# Tracker.net
KiCad netlist of a schematic drawn in EAGLE
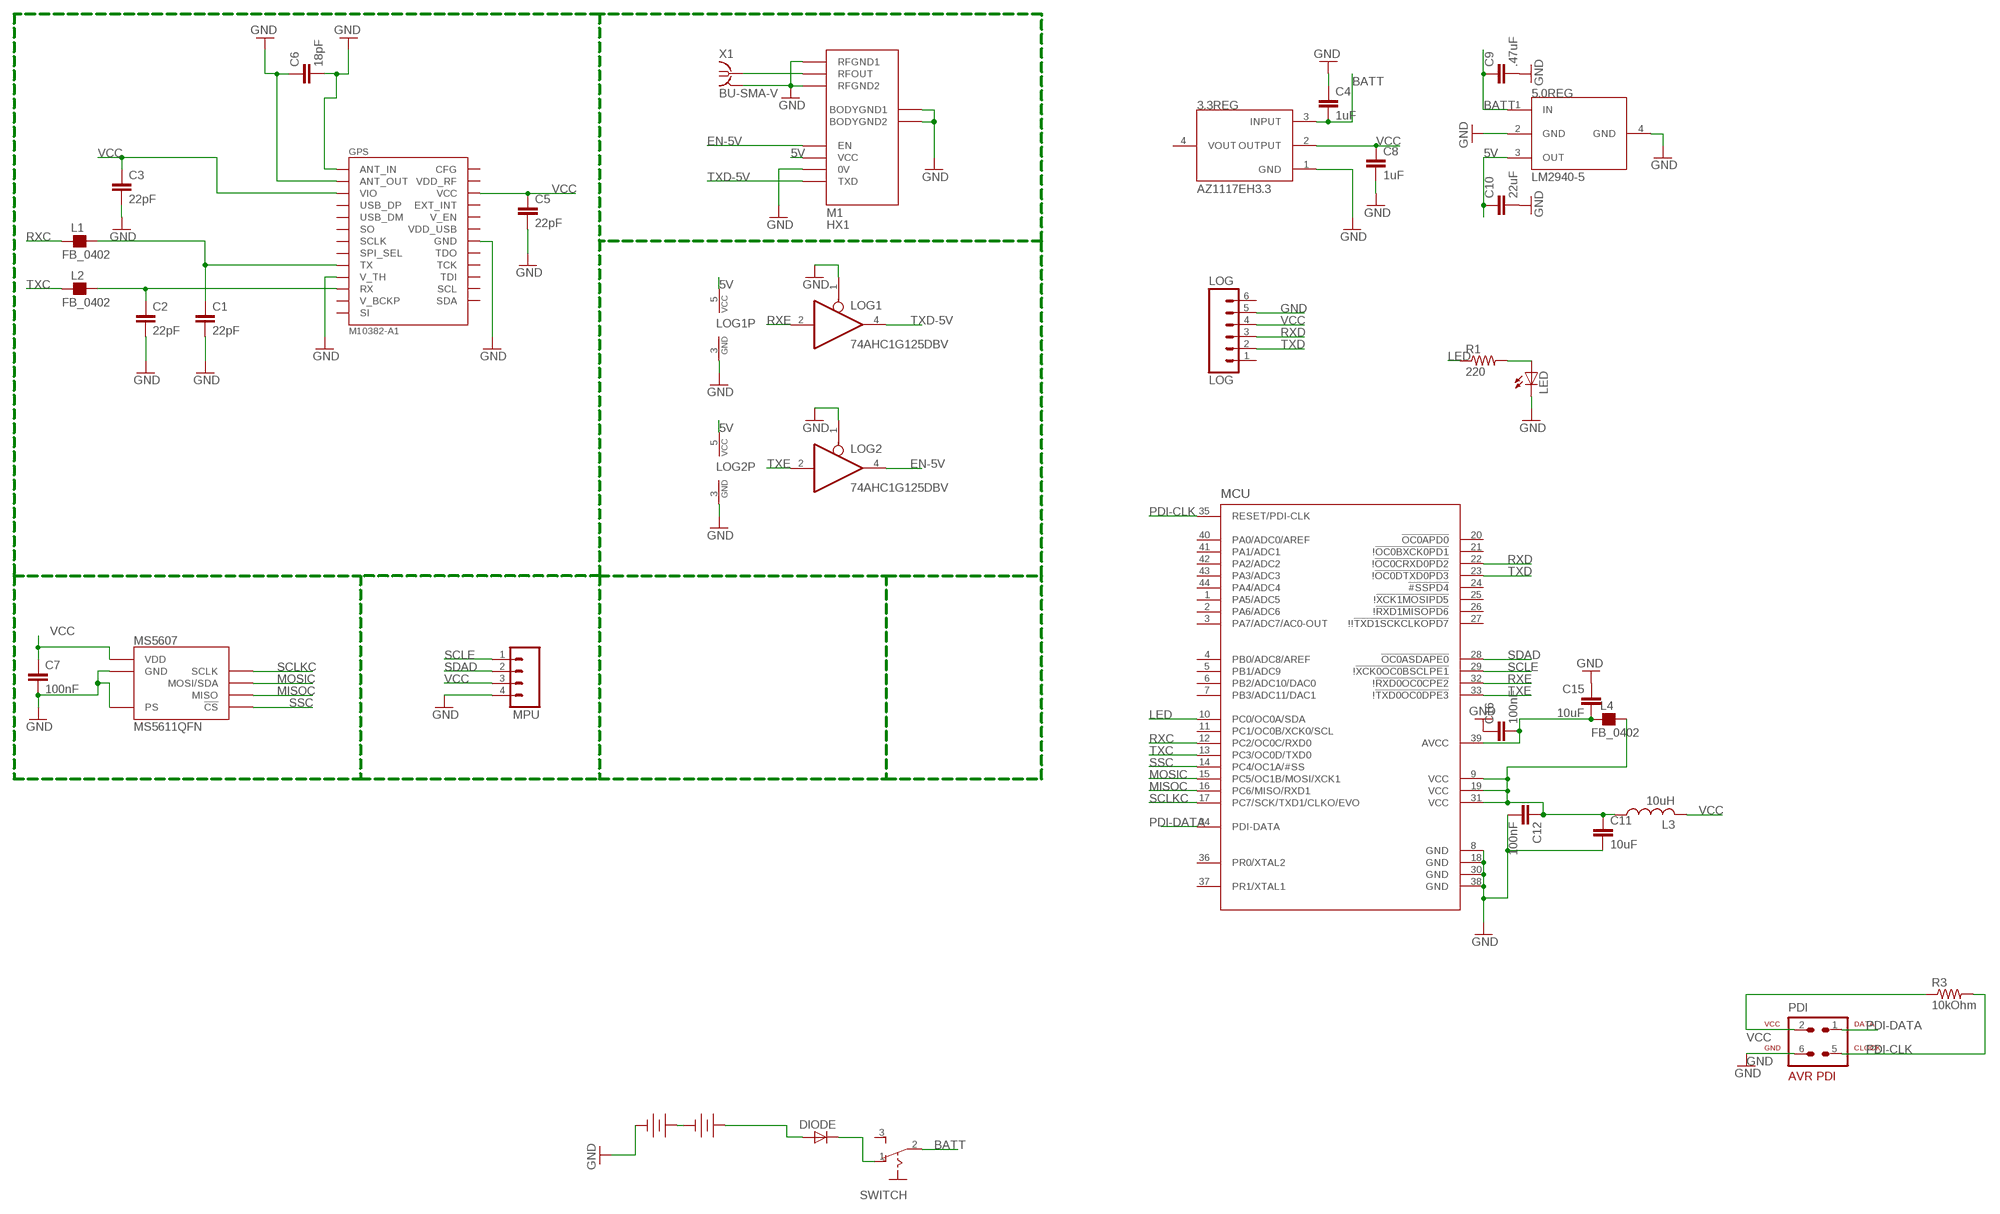
[diagram p0: schematic, sheet 1]

(export (version "E")
  (design (tool "Eeschema 10.0.6"))
  (components
    (comp (ref "3.3REG")
      (value "AZ1117EH3.3")
      (footprint "eagle-import:SOT-223")
      (libsource (lib "eagle-import") (part "AZ1117EH3.3"))
    )
    (comp (ref "5.0REG")
      (value "LM2940-5")
      (footprint "eagle-import:SOT-223")
      (libsource (lib "eagle-import") (part "LM2940-5"))
    )
    (comp (ref "BATT1")
      (value "123_BATTERY_HOLDERCR-123-A")
      (footprint "eagle-import:CR-123-A_HOLDER")
      (libsource (lib "eagle-import") (part "123_BATTERY_HOLDERCR-123-A"))
    )
    (comp (ref "BATT2")
      (value "123_BATTERY_HOLDERCR-123-A")
      (footprint "eagle-import:CR-123-A_HOLDER")
      (libsource (lib "eagle-import") (part "123_BATTERY_HOLDERCR-123-A"))
    )
    (comp (ref "C1")
      (value "22pF")
      (footprint "eagle-import:0805")
      (libsource (lib "eagle-import") (part "CAP0805"))
    )
    (comp (ref "C2")
      (value "22pF")
      (footprint "eagle-import:0805")
      (libsource (lib "eagle-import") (part "CAP0805"))
    )
    (comp (ref "C3")
      (value "22pF")
      (footprint "eagle-import:0805")
      (libsource (lib "eagle-import") (part "CAP0805"))
    )
    (comp (ref "C4")
      (value "1uF")
      (footprint "eagle-import:0603-CAP")
      (libsource (lib "eagle-import") (part "CAP0603-CAP"))
    )
    (comp (ref "C5")
      (value "22pF")
      (footprint "eagle-import:0805")
      (libsource (lib "eagle-import") (part "CAP0805"))
    )
    (comp (ref "C6")
      (value "18pF")
      (footprint "eagle-import:0805")
      (libsource (lib "eagle-import") (part "CAP0805"))
    )
    (comp (ref "C7")
      (value "100nF")
      (footprint "eagle-import:0805")
      (libsource (lib "eagle-import") (part "CAP0805"))
    )
    (comp (ref "C8")
      (value "1uF")
      (footprint "eagle-import:0603-CAP")
      (libsource (lib "eagle-import") (part "CAP0603-CAP"))
    )
    (comp (ref "C9")
      (value ".47uF")
      (footprint "eagle-import:0603-CAP")
      (libsource (lib "eagle-import") (part "CAP0603-CAP"))
    )
    (comp (ref "C10")
      (value "22uF")
      (footprint "eagle-import:0603-CAP")
      (libsource (lib "eagle-import") (part "CAP0603-CAP"))
    )
    (comp (ref "C11")
      (value "10uF")
      (footprint "eagle-import:0805")
      (libsource (lib "eagle-import") (part "CAP0805"))
    )
    (comp (ref "C12")
      (value "100nF")
      (footprint "eagle-import:0805")
      (libsource (lib "eagle-import") (part "CAP0805"))
    )
    (comp (ref "C15")
      (value "10uF")
      (footprint "eagle-import:0805")
      (libsource (lib "eagle-import") (part "CAP0805"))
    )
    (comp (ref "C16")
      (value "100nF")
      (footprint "eagle-import:0805")
      (libsource (lib "eagle-import") (part "CAP0805"))
    )
    (comp (ref "DIODE")
      (value "LILYPAD-WEARABLES_LED1206")
      (footprint "eagle-import:LILYPAD-WEARABLES_LED-1206")
      (libsource (lib "eagle-import") (part "LILYPAD-WEARABLES_LED1206"))
    )
    (comp (ref "GPS")
      (value "M10382-A1")
      (footprint "eagle-import:M10382-A1")
      (libsource (lib "eagle-import") (part "M10382-A1"))
    )
    (comp (ref "L1")
      (value "FB_0402")
      (footprint "eagle-import:L0402")
      (libsource (lib "eagle-import") (part "FB_0402"))
    )
    (comp (ref "L2")
      (value "FB_0402")
      (footprint "eagle-import:L0402")
      (libsource (lib "eagle-import") (part "FB_0402"))
    )
    (comp (ref "L3")
      (value "10uH")
      (footprint "eagle-import:L2012C")
      (libsource (lib "eagle-import") (part "L-USL2012C"))
    )
    (comp (ref "L4")
      (value "FB_0402")
      (footprint "eagle-import:L0402")
      (libsource (lib "eagle-import") (part "FB_0402"))
    )
    (comp (ref "LED")
      (value "LEDCHIP-LED0603")
      (footprint "eagle-import:CHIP-LED0603")
      (libsource (lib "eagle-import") (part "LEDCHIP-LED0603"))
    )
    (comp (ref "LOG")
      (value "LOG")
      (footprint "eagle-import:SPARKFUN_1X06")
      (libsource (lib "eagle-import") (part "SPARKFUN_M06SIP"))
    )
    (comp (ref "LOG1")
      (value "74AHC1G125DBV")
      (footprint "eagle-import:SOT23-5")
      (libsource (lib "eagle-import") (part "741G125DBVAHC"))
    )
    (comp (ref "LOG2")
      (value "74AHC1G125DBV")
      (footprint "eagle-import:SOT23-5")
      (libsource (lib "eagle-import") (part "741G125DBVAHC"))
    )
    (comp (ref "M1")
      (value "HX1")
      (footprint "eagle-import:HX1")
      (libsource (lib "eagle-import") (part "HX1"))
    )
    (comp (ref "MCU")
      (value "AT-XMEGA-XXA4-AU")
      (footprint "eagle-import:QFP80P1200X1200X120-44N")
      (libsource (lib "eagle-import") (part "AT-XMEGA-XXA4-AU"))
    )
    (comp (ref "MPU")
      (value "M04")
      (footprint "eagle-import:04P")
      (libsource (lib "eagle-import") (part "M04"))
    )
    (comp (ref "MS5607")
      (value "MS5611QFN")
      (footprint "eagle-import:MS5611-01BA01")
      (libsource (lib "eagle-import") (part "MS5611QFN"))
    )
    (comp (ref "PDI")
      (value "AVR-7_AVR-PDIVERT")
      (footprint "eagle-import:AVR-7_AVR-ISP-6")
      (libsource (lib "eagle-import") (part "AVR-7_AVR-PDIVERT"))
    )
    (comp (ref "R1")
      (value "220")
      (footprint "eagle-import:R0603")
      (libsource (lib "eagle-import") (part "R-US_R0603"))
    )
    (comp (ref "R3")
      (value "10kOhm")
      (footprint "eagle-import:0805")
      (libsource (lib "eagle-import") (part "RESISTOR0805-RES"))
    )
    (comp (ref "SWITCH")
      (value "M251")
      (footprint "eagle-import:M251")
      (libsource (lib "eagle-import") (part "M251"))
    )
    (comp (ref "X1")
      (value "BU-SMA-V")
      (footprint "eagle-import:BU-SMA-V")
      (libsource (lib "eagle-import") (part "BU-SMA-V"))
    )
  )
  (nets
    (net (code "1") (name "/5V") (class "Default")
      (node (ref "5.0REG") (pin "3") (pinfunction "OUT_3") (pintype "bidirectional"))
      (node (ref "C10") (pin "1") (pinfunction "1_1") (pintype "passive"))
      (node (ref "LOG1") (pin "5") (pinfunction "VCC_5") (pintype "power_in"))
      (node (ref "LOG2") (pin "5") (pinfunction "VCC_5") (pintype "power_in"))
      (node (ref "M1") (pin "VCC") (pinfunction "VCC_VCC") (pintype "bidirectional"))
    )
    (net (code "2") (name "/BATT") (class "Default")
      (node (ref "3.3REG") (pin "3") (pinfunction "INPUT_3") (pintype "bidirectional"))
      (node (ref "5.0REG") (pin "1") (pinfunction "IN_1") (pintype "bidirectional"))
      (node (ref "C4") (pin "2") (pinfunction "2_2") (pintype "passive"))
      (node (ref "C9") (pin "1") (pinfunction "1_1") (pintype "passive"))
      (node (ref "SWITCH") (pin "2") (pinfunction "P_2") (pintype "passive"))
    )
    (net (code "3") (name "/EN-5V") (class "Default")
      (node (ref "LOG2") (pin "4") (pinfunction "O_4") (pintype "tri_state"))
      (node (ref "M1") (pin "EN") (pinfunction "EN_EN") (pintype "bidirectional"))
    )
    (net (code "4") (name "/LED") (class "Default")
      (node (ref "MCU") (pin "10") (pinfunction "PC0/OC0A/SDA_10") (pintype "bidirectional"))
      (node (ref "R1") (pin "1") (pinfunction "1_1") (pintype "passive"))
    )
    (net (code "5") (name "/MISOC") (class "Default")
      (node (ref "MCU") (pin "16") (pinfunction "PC6/MISO/RXD1_16") (pintype "bidirectional"))
      (node (ref "MS5607") (pin "6") (pinfunction "MISO_6") (pintype "bidirectional"))
    )
    (net (code "6") (name "/MOSIC") (class "Default")
      (node (ref "MCU") (pin "15") (pinfunction "PC5/OC1B/MOSI/XCK1_15") (pintype "bidirectional"))
      (node (ref "MS5607") (pin "7") (pinfunction "MOSI/SDA_7") (pintype "bidirectional"))
    )
    (net (code "7") (name "/PDI-CLK") (class "Default")
      (node (ref "MCU") (pin "35") (pinfunction "RESET/PDI-CLK_35") (pintype "input"))
      (node (ref "PDI") (pin "5") (pinfunction "5_5") (pintype "passive"))
      (node (ref "R3") (pin "2") (pinfunction "2_2") (pintype "passive"))
    )
    (net (code "8") (name "/PDI-DATA") (class "Default")
      (node (ref "MCU") (pin "34") (pinfunction "PDI-DATA_34") (pintype "bidirectional"))
      (node (ref "PDI") (pin "1") (pinfunction "1_1") (pintype "passive"))
    )
    (net (code "9") (name "/RXC") (class "Default")
      (node (ref "L1") (pin "1") (pinfunction "1_1") (pintype "passive"))
      (node (ref "MCU") (pin "12") (pinfunction "PC2/OC0C/RXD0_12") (pintype "bidirectional"))
    )
    (net (code "10") (name "/RXD") (class "Default")
      (node (ref "LOG") (pin "3") (pinfunction "3_3") (pintype "passive"))
      (node (ref "MCU") (pin "22") (pinfunction "~OC0CRXD0PD2_22") (pintype "bidirectional"))
    )
    (net (code "11") (name "/RXE") (class "Default")
      (node (ref "LOG1") (pin "2") (pinfunction "I_2") (pintype "input"))
      (node (ref "MCU") (pin "32") (pinfunction "~RXD0OC0CPE2_32") (pintype "bidirectional"))
    )
    (net (code "12") (name "/SCLE") (class "Default")
      (node (ref "MCU") (pin "29") (pinfunction "~XCK0OC0BSCLPE1_29") (pintype "bidirectional"))
      (node (ref "MPU") (pin "1") (pinfunction "1_1") (pintype "passive"))
    )
    (net (code "13") (name "/SCLKC") (class "Default")
      (node (ref "MCU") (pin "17") (pinfunction "PC7/SCK/TXD1/CLKO/EVO_17") (pintype "bidirectional"))
      (node (ref "MS5607") (pin "8") (pinfunction "SCLK_8") (pintype "bidirectional"))
    )
    (net (code "14") (name "/SDAD") (class "Default")
      (node (ref "MCU") (pin "28") (pinfunction "~{OC0ASDAPE0}_28") (pintype "bidirectional"))
      (node (ref "MPU") (pin "2") (pinfunction "2_2") (pintype "passive"))
    )
    (net (code "15") (name "/SSC") (class "Default")
      (node (ref "MCU") (pin "14") (pinfunction "PC4/OC1A/#SS_14") (pintype "bidirectional"))
      (node (ref "MS5607") (pin "4") (pinfunction "~{CS}_4") (pintype "bidirectional"))
      (node (ref "MS5607") (pin "5") (pinfunction "~{CS}_5") (pintype "bidirectional"))
    )
    (net (code "16") (name "/TXC") (class "Default")
      (node (ref "L2") (pin "1") (pinfunction "1_1") (pintype "passive"))
      (node (ref "MCU") (pin "13") (pinfunction "PC3/OC0D/TXD0_13") (pintype "bidirectional"))
    )
    (net (code "17") (name "/TXD") (class "Default")
      (node (ref "LOG") (pin "2") (pinfunction "2_2") (pintype "passive"))
      (node (ref "MCU") (pin "23") (pinfunction "~OC0DTXD0PD3_23") (pintype "bidirectional"))
    )
    (net (code "18") (name "/TXD-5V") (class "Default")
      (node (ref "LOG1") (pin "4") (pinfunction "O_4") (pintype "tri_state"))
      (node (ref "M1") (pin "TXD") (pinfunction "TXD_TXD") (pintype "bidirectional"))
    )
    (net (code "19") (name "/TXE") (class "Default")
      (node (ref "LOG2") (pin "2") (pinfunction "I_2") (pintype "input"))
      (node (ref "MCU") (pin "33") (pinfunction "~TXD0OC0DPE3_33") (pintype "bidirectional"))
    )
    (net (code "20") (name "/VCC") (class "Default")
      (node (ref "3.3REG") (pin "2") (pinfunction "OUTPUT_2") (pintype "bidirectional"))
      (node (ref "C3") (pin "1") (pinfunction "1_1") (pintype "passive"))
      (node (ref "C5") (pin "1") (pinfunction "1_1") (pintype "passive"))
      (node (ref "C7") (pin "1") (pinfunction "1_1") (pintype "passive"))
      (node (ref "C8") (pin "1") (pinfunction "1_1") (pintype "passive"))
      (node (ref "GPS") (pin "27") (pinfunction "VCC_27") (pintype "bidirectional"))
      (node (ref "GPS") (pin "5") (pinfunction "VIO_5") (pintype "bidirectional"))
      (node (ref "L3") (pin "2") (pinfunction "2_2") (pintype "passive"))
      (node (ref "LOG") (pin "4") (pinfunction "4_4") (pintype "passive"))
      (node (ref "MPU") (pin "3") (pinfunction "3_3") (pintype "passive"))
      (node (ref "MS5607") (pin "1") (pinfunction "VDD_1") (pintype "bidirectional"))
      (node (ref "PDI") (pin "2") (pinfunction "2_2") (pintype "passive"))
      (node (ref "R3") (pin "1") (pinfunction "1_1") (pintype "passive"))
    )
    (net (code "21") (name "GND") (class "Default")
      (node (ref "3.3REG") (pin "1") (pinfunction "GND_1") (pintype "bidirectional"))
      (node (ref "5.0REG") (pin "2") (pinfunction "GND_2") (pintype "bidirectional"))
      (node (ref "5.0REG") (pin "4") (pinfunction "GND_4") (pintype "bidirectional"))
      (node (ref "BATT2") (pin "-") (pinfunction "-_-") (pintype "bidirectional"))
      (node (ref "C1") (pin "2") (pinfunction "2_2") (pintype "passive"))
      (node (ref "C10") (pin "2") (pinfunction "2_2") (pintype "passive"))
      (node (ref "C11") (pin "2") (pinfunction "2_2") (pintype "passive"))
      (node (ref "C12") (pin "2") (pinfunction "2_2") (pintype "passive"))
      (node (ref "C15") (pin "1") (pinfunction "1_1") (pintype "passive"))
      (node (ref "C16") (pin "1") (pinfunction "1_1") (pintype "passive"))
      (node (ref "C2") (pin "2") (pinfunction "2_2") (pintype "passive"))
      (node (ref "C3") (pin "2") (pinfunction "2_2") (pintype "passive"))
      (node (ref "C4") (pin "1") (pinfunction "1_1") (pintype "passive"))
      (node (ref "C5") (pin "2") (pinfunction "2_2") (pintype "passive"))
      (node (ref "C6") (pin "1") (pinfunction "1_1") (pintype "passive"))
      (node (ref "C6") (pin "2") (pinfunction "2_2") (pintype "passive"))
      (node (ref "C7") (pin "2") (pinfunction "2_2") (pintype "passive"))
      (node (ref "C8") (pin "2") (pinfunction "2_2") (pintype "passive"))
      (node (ref "C9") (pin "2") (pinfunction "2_2") (pintype "passive"))
      (node (ref "GPS") (pin "1") (pinfunction "ANT_IN_1") (pintype "bidirectional"))
      (node (ref "GPS") (pin "12") (pinfunction "V_TH_12") (pintype "bidirectional"))
      (node (ref "GPS") (pin "14") (pinfunction "GND_14") (pintype "bidirectional"))
      (node (ref "GPS") (pin "17") (pinfunction "GND_17") (pintype "bidirectional"))
      (node (ref "GPS") (pin "2") (pinfunction "GND_2") (pintype "bidirectional"))
      (node (ref "GPS") (pin "21") (pinfunction "GND_21") (pintype "bidirectional"))
      (node (ref "GPS") (pin "24") (pinfunction "GND_24") (pintype "bidirectional"))
      (node (ref "GPS") (pin "26") (pinfunction "GND_26") (pintype "bidirectional"))
      (node (ref "GPS") (pin "28") (pinfunction "GND_28") (pintype "bidirectional"))
      (node (ref "GPS") (pin "3") (pinfunction "ANT_OUT_3") (pintype "bidirectional"))
      (node (ref "GPS") (pin "33") (pinfunction "GND_33") (pintype "bidirectional"))
      (node (ref "GPS") (pin "34") (pinfunction "GND_34") (pintype "bidirectional"))
      (node (ref "GPS") (pin "35") (pinfunction "GND_35") (pintype "bidirectional"))
      (node (ref "GPS") (pin "36") (pinfunction "GND_36") (pintype "bidirectional"))
      (node (ref "GPS") (pin "4") (pinfunction "GND_4") (pintype "bidirectional"))
      (node (ref "LED") (pin "C") (pinfunction "C_C") (pintype "passive"))
      (node (ref "LOG") (pin "5") (pinfunction "5_5") (pintype "passive"))
      (node (ref "LOG1") (pin "1") (pinfunction "OE_1") (pintype "input"))
      (node (ref "LOG1") (pin "3") (pinfunction "GND_3") (pintype "power_in"))
      (node (ref "LOG2") (pin "1") (pinfunction "OE_1") (pintype "input"))
      (node (ref "LOG2") (pin "3") (pinfunction "GND_3") (pintype "power_in"))
      (node (ref "M1") (pin "0V") (pinfunction "0V_0V") (pintype "bidirectional"))
      (node (ref "M1") (pin "BODYGND1") (pinfunction "BODYGND1_BODYGND1") (pintype "bidirectional"))
      (node (ref "M1") (pin "BODYGND2") (pinfunction "BODYGND2_BODYGND2") (pintype "bidirectional"))
      (node (ref "M1") (pin "RFGND1") (pinfunction "RFGND1_RFGND1") (pintype "bidirectional"))
      (node (ref "M1") (pin "RFGND2") (pinfunction "RFGND2_RFGND2") (pintype "bidirectional"))
      (node (ref "MCU") (pin "18") (pinfunction "GND_18") (pintype "power_in"))
      (node (ref "MCU") (pin "30") (pinfunction "GND_30") (pintype "power_in"))
      (node (ref "MCU") (pin "38") (pinfunction "GND_38") (pintype "power_in"))
      (node (ref "MCU") (pin "8") (pinfunction "GND_8") (pintype "power_in"))
      (node (ref "MPU") (pin "4") (pinfunction "4_4") (pintype "passive"))
      (node (ref "MS5607") (pin "2") (pinfunction "PS_2") (pintype "bidirectional"))
      (node (ref "MS5607") (pin "3") (pinfunction "GND_3") (pintype "bidirectional"))
      (node (ref "PDI") (pin "6") (pinfunction "6_6") (pintype "passive"))
      (node (ref "X1") (pin "2") (pinfunction "GND_2") (pintype "power_in"))
    )
    (net (code "22") (name "Net-(BATT1-Pad+)") (class "Default")
      (node (ref "BATT1") (pin "+") (pinfunction "+_+") (pintype "bidirectional"))
      (node (ref "DIODE") (pin "A") (pinfunction "A_A") (pintype "passive"))
    )
    (net (code "23") (name "Net-(BATT1-Pad-)") (class "Default")
      (node (ref "BATT1") (pin "-") (pinfunction "-_-") (pintype "bidirectional"))
      (node (ref "BATT2") (pin "+") (pinfunction "+_+") (pintype "bidirectional"))
    )
    (net (code "24") (name "Net-(C11-Pad1)") (class "Default")
      (node (ref "C11") (pin "1") (pinfunction "1_1") (pintype "passive"))
      (node (ref "C12") (pin "1") (pinfunction "1_1") (pintype "passive"))
      (node (ref "L3") (pin "1") (pinfunction "1_1") (pintype "passive"))
      (node (ref "L4") (pin "2") (pinfunction "2_2") (pintype "passive"))
      (node (ref "MCU") (pin "19") (pinfunction "VCC_19") (pintype "power_in"))
      (node (ref "MCU") (pin "31") (pinfunction "VCC_31") (pintype "power_in"))
      (node (ref "MCU") (pin "9") (pinfunction "VCC_9") (pintype "power_in"))
    )
    (net (code "25") (name "Net-(GPS-RX)") (class "Default")
      (node (ref "C2") (pin "1") (pinfunction "1_1") (pintype "passive"))
      (node (ref "GPS") (pin "13") (pinfunction "RX_13") (pintype "bidirectional"))
      (node (ref "L2") (pin "2") (pinfunction "2_2") (pintype "passive"))
    )
    (net (code "26") (name "Net-(GPS-TX)") (class "Default")
      (node (ref "C1") (pin "1") (pinfunction "1_1") (pintype "passive"))
      (node (ref "GPS") (pin "11") (pinfunction "TX_11") (pintype "bidirectional"))
      (node (ref "L1") (pin "2") (pinfunction "2_2") (pintype "passive"))
    )
    (net (code "27") (name "Net-(LED-PadA)") (class "Default")
      (node (ref "LED") (pin "A") (pinfunction "A_A") (pintype "passive"))
      (node (ref "R1") (pin "2") (pinfunction "2_2") (pintype "passive"))
    )
    (net (code "28") (name "Net-(M1-PadRFOUT)") (class "Default")
      (node (ref "M1") (pin "RFOUT") (pinfunction "RFOUT_RFOUT") (pintype "bidirectional"))
      (node (ref "X1") (pin "1") (pinfunction "1_1") (pintype "passive"))
    )
    (net (code "29") (name "Net-(MCU-AVCC)") (class "Default")
      (node (ref "C15") (pin "2") (pinfunction "2_2") (pintype "passive"))
      (node (ref "C16") (pin "2") (pinfunction "2_2") (pintype "passive"))
      (node (ref "L4") (pin "1") (pinfunction "1_1") (pintype "passive"))
      (node (ref "MCU") (pin "39") (pinfunction "AVCC_39") (pintype "power_in"))
    )
    (net (code "30") (name "Net-(SWITCH-O)") (class "Default")
      (node (ref "DIODE") (pin "C") (pinfunction "C_C") (pintype "passive"))
      (node (ref "SWITCH") (pin "1") (pinfunction "O_1") (pintype "passive"))
    )
    (net (code "31") (name "unconnected-(3.3REG-VOUT-Pad4)") (class "Default")
      (node (ref "3.3REG") (pin "4") (pinfunction "VOUT_4") (pintype "bidirectional"))
    )
    (net (code "32") (name "unconnected-(GPS-CFG-Pad31)") (class "Default")
      (node (ref "GPS") (pin "31") (pinfunction "CFG_31") (pintype "bidirectional"))
    )
    (net (code "33") (name "unconnected-(GPS-EXT_INT-Pad29)") (class "Default")
      (node (ref "GPS") (pin "29") (pinfunction "EXT_INT_29") (pintype "bidirectional"))
    )
    (net (code "34") (name "unconnected-(GPS-SCL-Pad19)") (class "Default")
      (node (ref "GPS") (pin "19") (pinfunction "SCL_19") (pintype "bidirectional"))
    )
    (net (code "35") (name "unconnected-(GPS-SCLK-Pad9)") (class "Default")
      (node (ref "GPS") (pin "9") (pinfunction "SCLK_9") (pintype "bidirectional"))
    )
    (net (code "36") (name "unconnected-(GPS-SDA-Pad18)") (class "Default")
      (node (ref "GPS") (pin "18") (pinfunction "SDA_18") (pintype "bidirectional"))
    )
    (net (code "37") (name "unconnected-(GPS-SI-Pad16)") (class "Default")
      (node (ref "GPS") (pin "16") (pinfunction "SI_16") (pintype "bidirectional"))
    )
    (net (code "38") (name "unconnected-(GPS-SO-Pad8)") (class "Default")
      (node (ref "GPS") (pin "8") (pinfunction "SO_8") (pintype "bidirectional"))
    )
    (net (code "39") (name "unconnected-(GPS-SPI_SEL-Pad10)") (class "Default")
      (node (ref "GPS") (pin "10") (pinfunction "SPI_SEL_10") (pintype "bidirectional"))
    )
    (net (code "40") (name "unconnected-(GPS-TCK-Pad22)") (class "Default")
      (node (ref "GPS") (pin "22") (pinfunction "TCK_22") (pintype "bidirectional"))
    )
    (net (code "41") (name "unconnected-(GPS-TDI-Pad20)") (class "Default")
      (node (ref "GPS") (pin "20") (pinfunction "TDI_20") (pintype "bidirectional"))
    )
    (net (code "42") (name "unconnected-(GPS-TDO-Pad23)") (class "Default")
      (node (ref "GPS") (pin "23") (pinfunction "TDO_23") (pintype "bidirectional"))
    )
    (net (code "43") (name "unconnected-(GPS-USB_DM-Pad7)") (class "Default")
      (node (ref "GPS") (pin "7") (pinfunction "USB_DM_7") (pintype "bidirectional"))
    )
    (net (code "44") (name "unconnected-(GPS-USB_DP-Pad6)") (class "Default")
      (node (ref "GPS") (pin "6") (pinfunction "USB_DP_6") (pintype "bidirectional"))
    )
    (net (code "45") (name "unconnected-(GPS-VDD_RF-Pad25)") (class "Default")
      (node (ref "GPS") (pin "25") (pinfunction "VDD_RF_25") (pintype "bidirectional"))
    )
    (net (code "46") (name "unconnected-(GPS-VDD_USB-Pad32)") (class "Default")
      (node (ref "GPS") (pin "32") (pinfunction "VDD_USB_32") (pintype "bidirectional"))
    )
    (net (code "47") (name "unconnected-(GPS-V_BCKP-Pad15)") (class "Default")
      (node (ref "GPS") (pin "15") (pinfunction "V_BCKP_15") (pintype "bidirectional"))
    )
    (net (code "48") (name "unconnected-(GPS-V_EN-Pad30)") (class "Default")
      (node (ref "GPS") (pin "30") (pinfunction "V_EN_30") (pintype "bidirectional"))
    )
    (net (code "49") (name "unconnected-(LOG-Pad1)") (class "Default")
      (node (ref "LOG") (pin "1") (pinfunction "1_1") (pintype "passive"))
    )
    (net (code "50") (name "unconnected-(LOG-Pad6)") (class "Default")
      (node (ref "LOG") (pin "6") (pinfunction "6_6") (pintype "passive"))
    )
    (net (code "51") (name "unconnected-(MCU-PA0{slash}ADC0{slash}AREF-Pad40)") (class "Default")
      (node (ref "MCU") (pin "40") (pinfunction "PA0/ADC0/AREF_40") (pintype "bidirectional"))
    )
    (net (code "52") (name "unconnected-(MCU-PA1{slash}ADC1-Pad41)") (class "Default")
      (node (ref "MCU") (pin "41") (pinfunction "PA1/ADC1_41") (pintype "bidirectional"))
    )
    (net (code "53") (name "unconnected-(MCU-PA2{slash}ADC2-Pad42)") (class "Default")
      (node (ref "MCU") (pin "42") (pinfunction "PA2/ADC2_42") (pintype "bidirectional"))
    )
    (net (code "54") (name "unconnected-(MCU-PA3{slash}ADC3-Pad43)") (class "Default")
      (node (ref "MCU") (pin "43") (pinfunction "PA3/ADC3_43") (pintype "bidirectional"))
    )
    (net (code "55") (name "unconnected-(MCU-PA4{slash}ADC4-Pad44)") (class "Default")
      (node (ref "MCU") (pin "44") (pinfunction "PA4/ADC4_44") (pintype "bidirectional"))
    )
    (net (code "56") (name "unconnected-(MCU-PA5{slash}ADC5-Pad1)") (class "Default")
      (node (ref "MCU") (pin "1") (pinfunction "PA5/ADC5_1") (pintype "bidirectional"))
    )
    (net (code "57") (name "unconnected-(MCU-PA6{slash}ADC6-Pad2)") (class "Default")
      (node (ref "MCU") (pin "2") (pinfunction "PA6/ADC6_2") (pintype "bidirectional"))
    )
    (net (code "58") (name "unconnected-(MCU-PA7{slash}ADC7{slash}AC0-OUT-Pad3)") (class "Default")
      (node (ref "MCU") (pin "3") (pinfunction "PA7/ADC7/AC0-OUT_3") (pintype "bidirectional"))
    )
    (net (code "59") (name "unconnected-(MCU-PB0{slash}ADC8{slash}AREF-Pad4)") (class "Default")
      (node (ref "MCU") (pin "4") (pinfunction "PB0/ADC8/AREF_4") (pintype "bidirectional"))
    )
    (net (code "60") (name "unconnected-(MCU-PB1{slash}ADC9-Pad5)") (class "Default")
      (node (ref "MCU") (pin "5") (pinfunction "PB1/ADC9_5") (pintype "bidirectional"))
    )
    (net (code "61") (name "unconnected-(MCU-PB2{slash}ADC10{slash}DAC0-Pad6)") (class "Default")
      (node (ref "MCU") (pin "6") (pinfunction "PB2/ADC10/DAC0_6") (pintype "bidirectional"))
    )
    (net (code "62") (name "unconnected-(MCU-PB3{slash}ADC11{slash}DAC1-Pad7)") (class "Default")
      (node (ref "MCU") (pin "7") (pinfunction "PB3/ADC11/DAC1_7") (pintype "bidirectional"))
    )
    (net (code "63") (name "unconnected-(MCU-PC1{slash}OC0B{slash}XCK0{slash}SCL-Pad11)") (class "Default")
      (node (ref "MCU") (pin "11") (pinfunction "PC1/OC0B/XCK0/SCL_11") (pintype "bidirectional"))
    )
    (net (code "64") (name "unconnected-(MCU-PR0{slash}XTAL2-Pad36)") (class "Default")
      (node (ref "MCU") (pin "36") (pinfunction "PR0/XTAL2_36") (pintype "bidirectional"))
    )
    (net (code "65") (name "unconnected-(MCU-PR1{slash}XTAL1-Pad37)") (class "Default")
      (node (ref "MCU") (pin "37") (pinfunction "PR1/XTAL1_37") (pintype "bidirectional"))
    )
    (net (code "66") (name "unconnected-(MCU-~OC0BXCK0PD1-Pad21)") (class "Default")
      (node (ref "MCU") (pin "21") (pinfunction "~OC0BXCK0PD1_21") (pintype "bidirectional"))
    )
    (net (code "67") (name "unconnected-(MCU-~RXD1MISOPD6-Pad26)") (class "Default")
      (node (ref "MCU") (pin "26") (pinfunction "~RXD1MISOPD6_26") (pintype "bidirectional"))
    )
    (net (code "68") (name "unconnected-(MCU-~XCK1MOSIPD5-Pad25)") (class "Default")
      (node (ref "MCU") (pin "25") (pinfunction "~XCK1MOSIPD5_25") (pintype "bidirectional"))
    )
    (net (code "69") (name "unconnected-(MCU-~{#SSPD4}-Pad24)") (class "Default")
      (node (ref "MCU") (pin "24") (pinfunction "~{#SSPD4}_24") (pintype "bidirectional"))
    )
    (net (code "70") (name "unconnected-(MCU-~{OC0APD0}-Pad20)") (class "Default")
      (node (ref "MCU") (pin "20") (pinfunction "~{OC0APD0}_20") (pintype "bidirectional"))
    )
    (net (code "71") (name "unconnected-(MCU-~~{TXD1SCKCLKOPD7}-Pad27)") (class "Default")
      (node (ref "MCU") (pin "27") (pinfunction "~~{TXD1SCKCLKOPD7}_27") (pintype "bidirectional"))
    )
    (net (code "72") (name "unconnected-(SWITCH-S-Pad3)") (class "Default")
      (node (ref "SWITCH") (pin "3") (pinfunction "S_3") (pintype "passive"))
    )
  )
)
